# StandaloneAnemometer_RevB.net
KiCad netlist of a schematic drawn in EAGLE
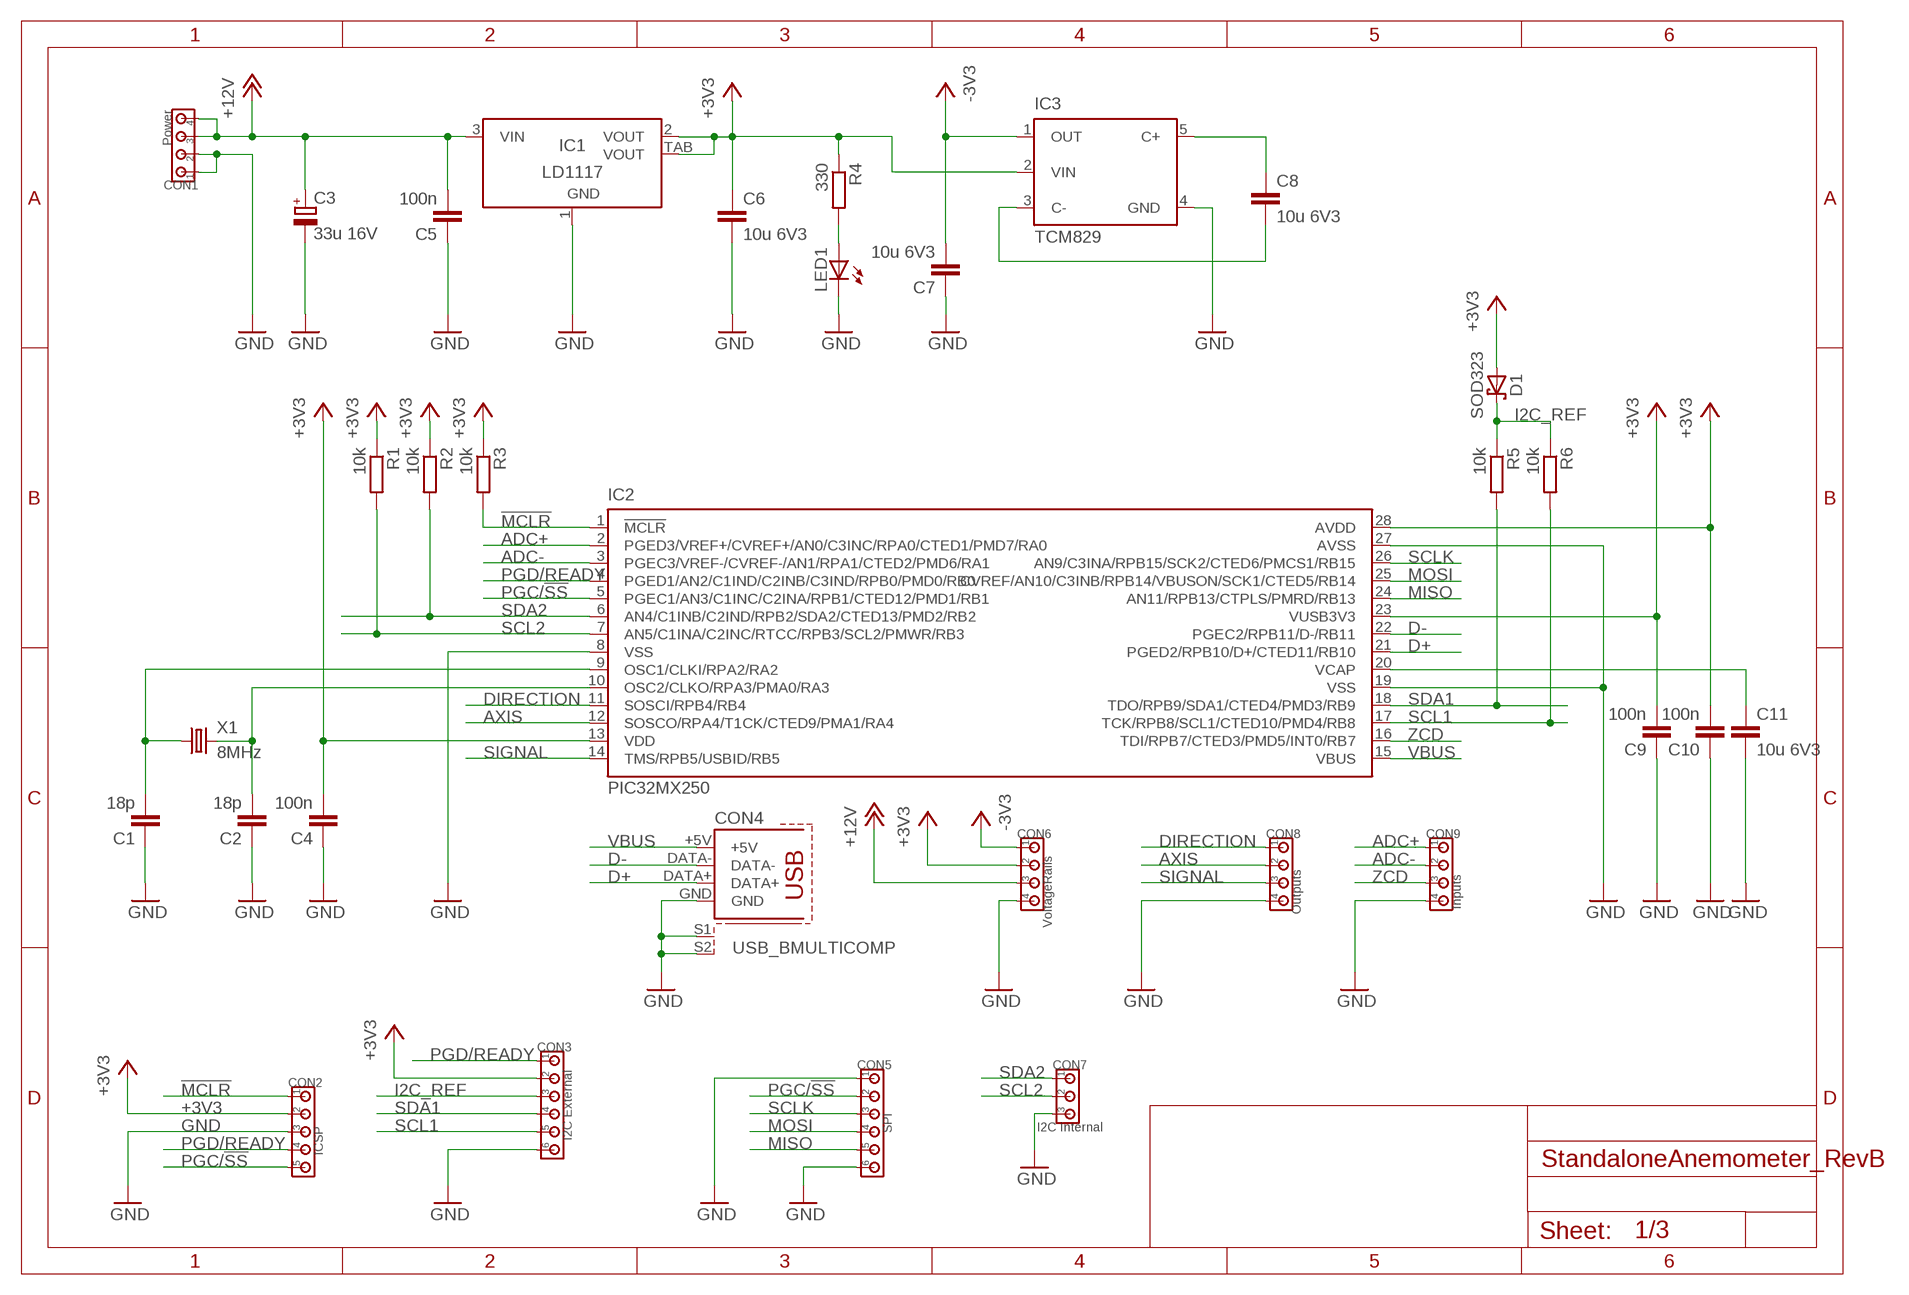
[diagram p0: schematic, sheet 1]
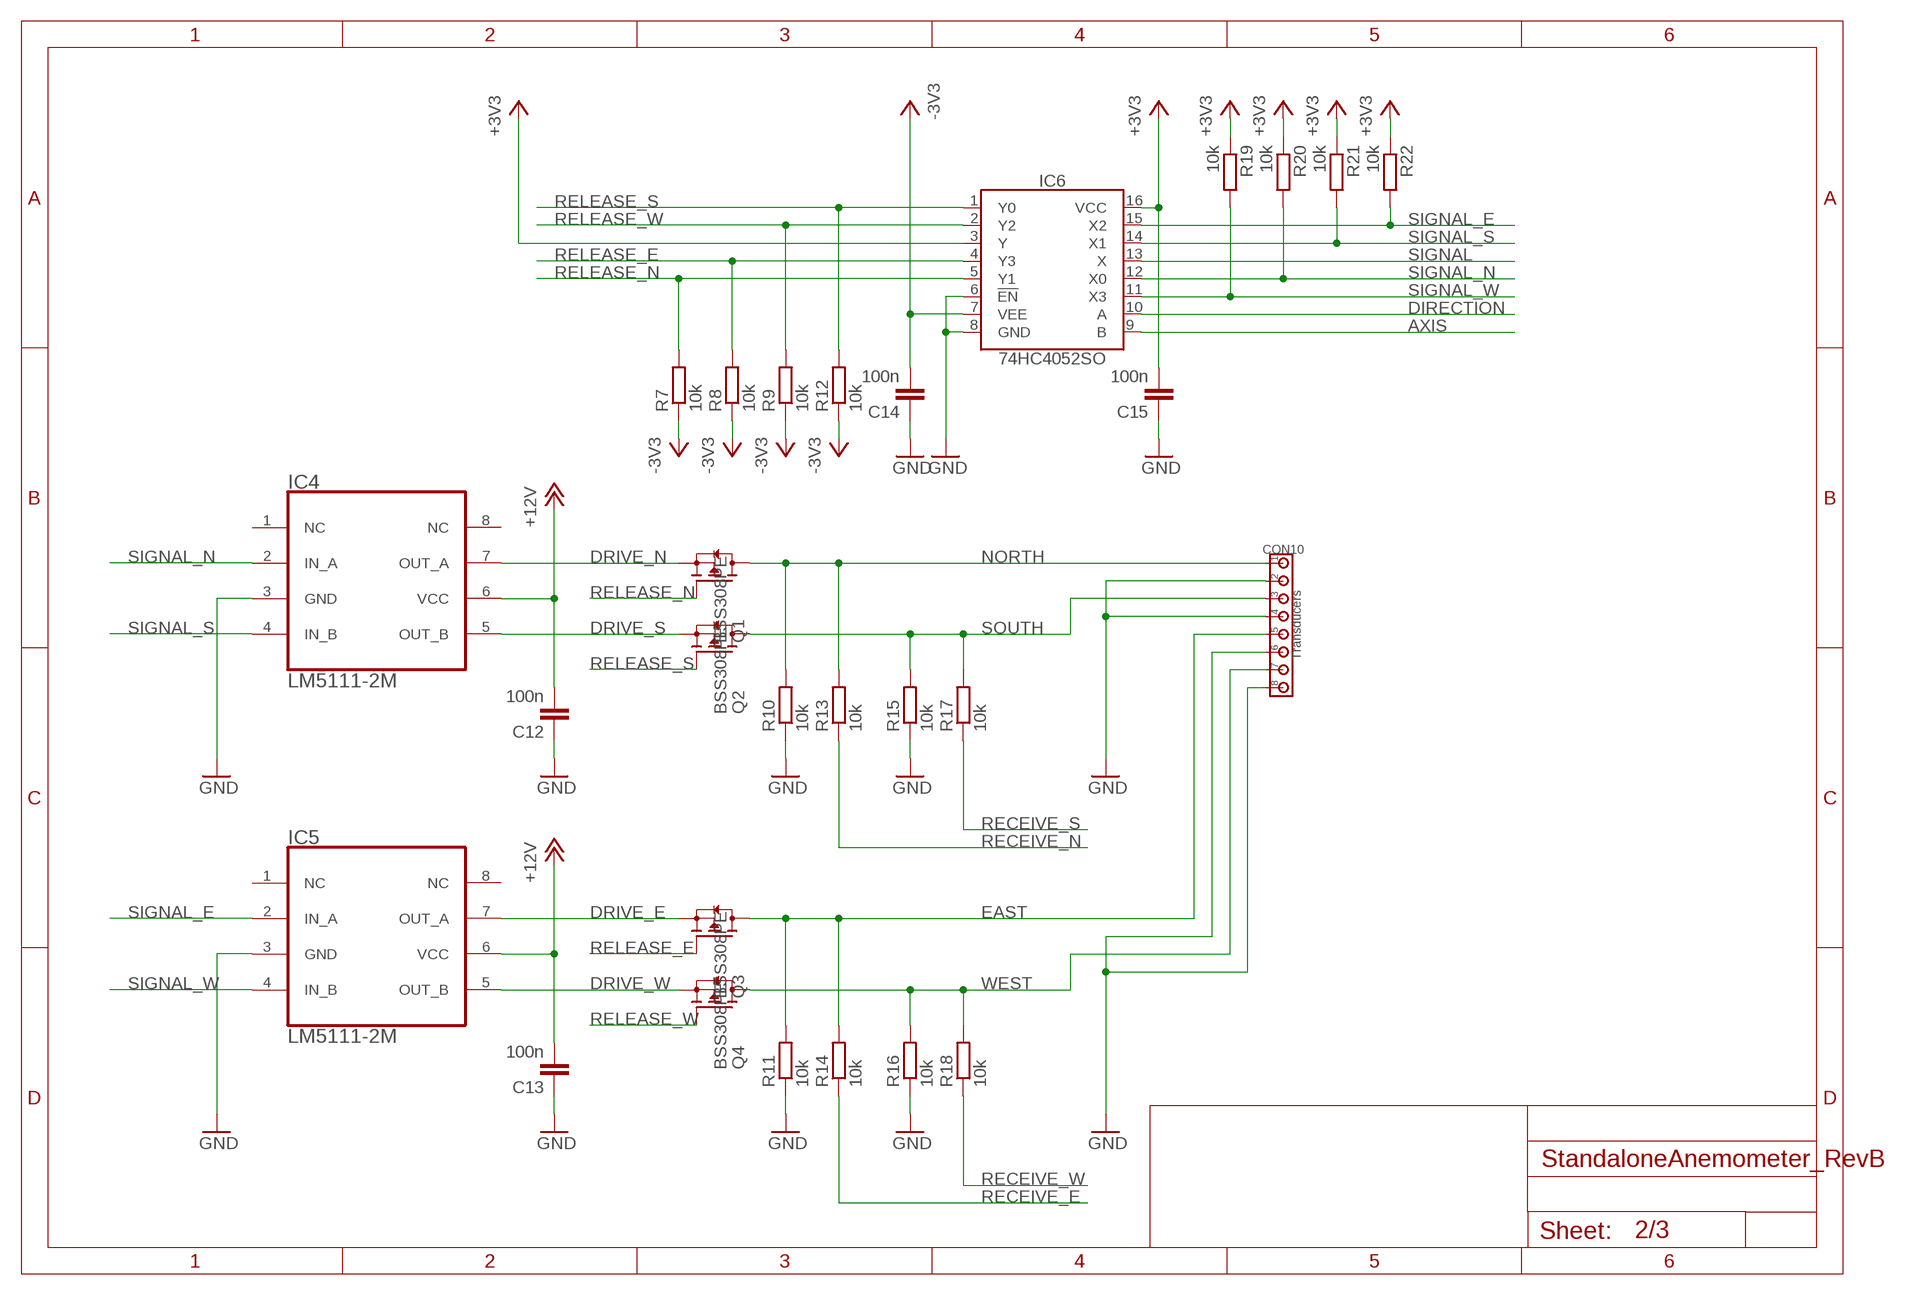
[diagram p1: schematic, sheet 2]
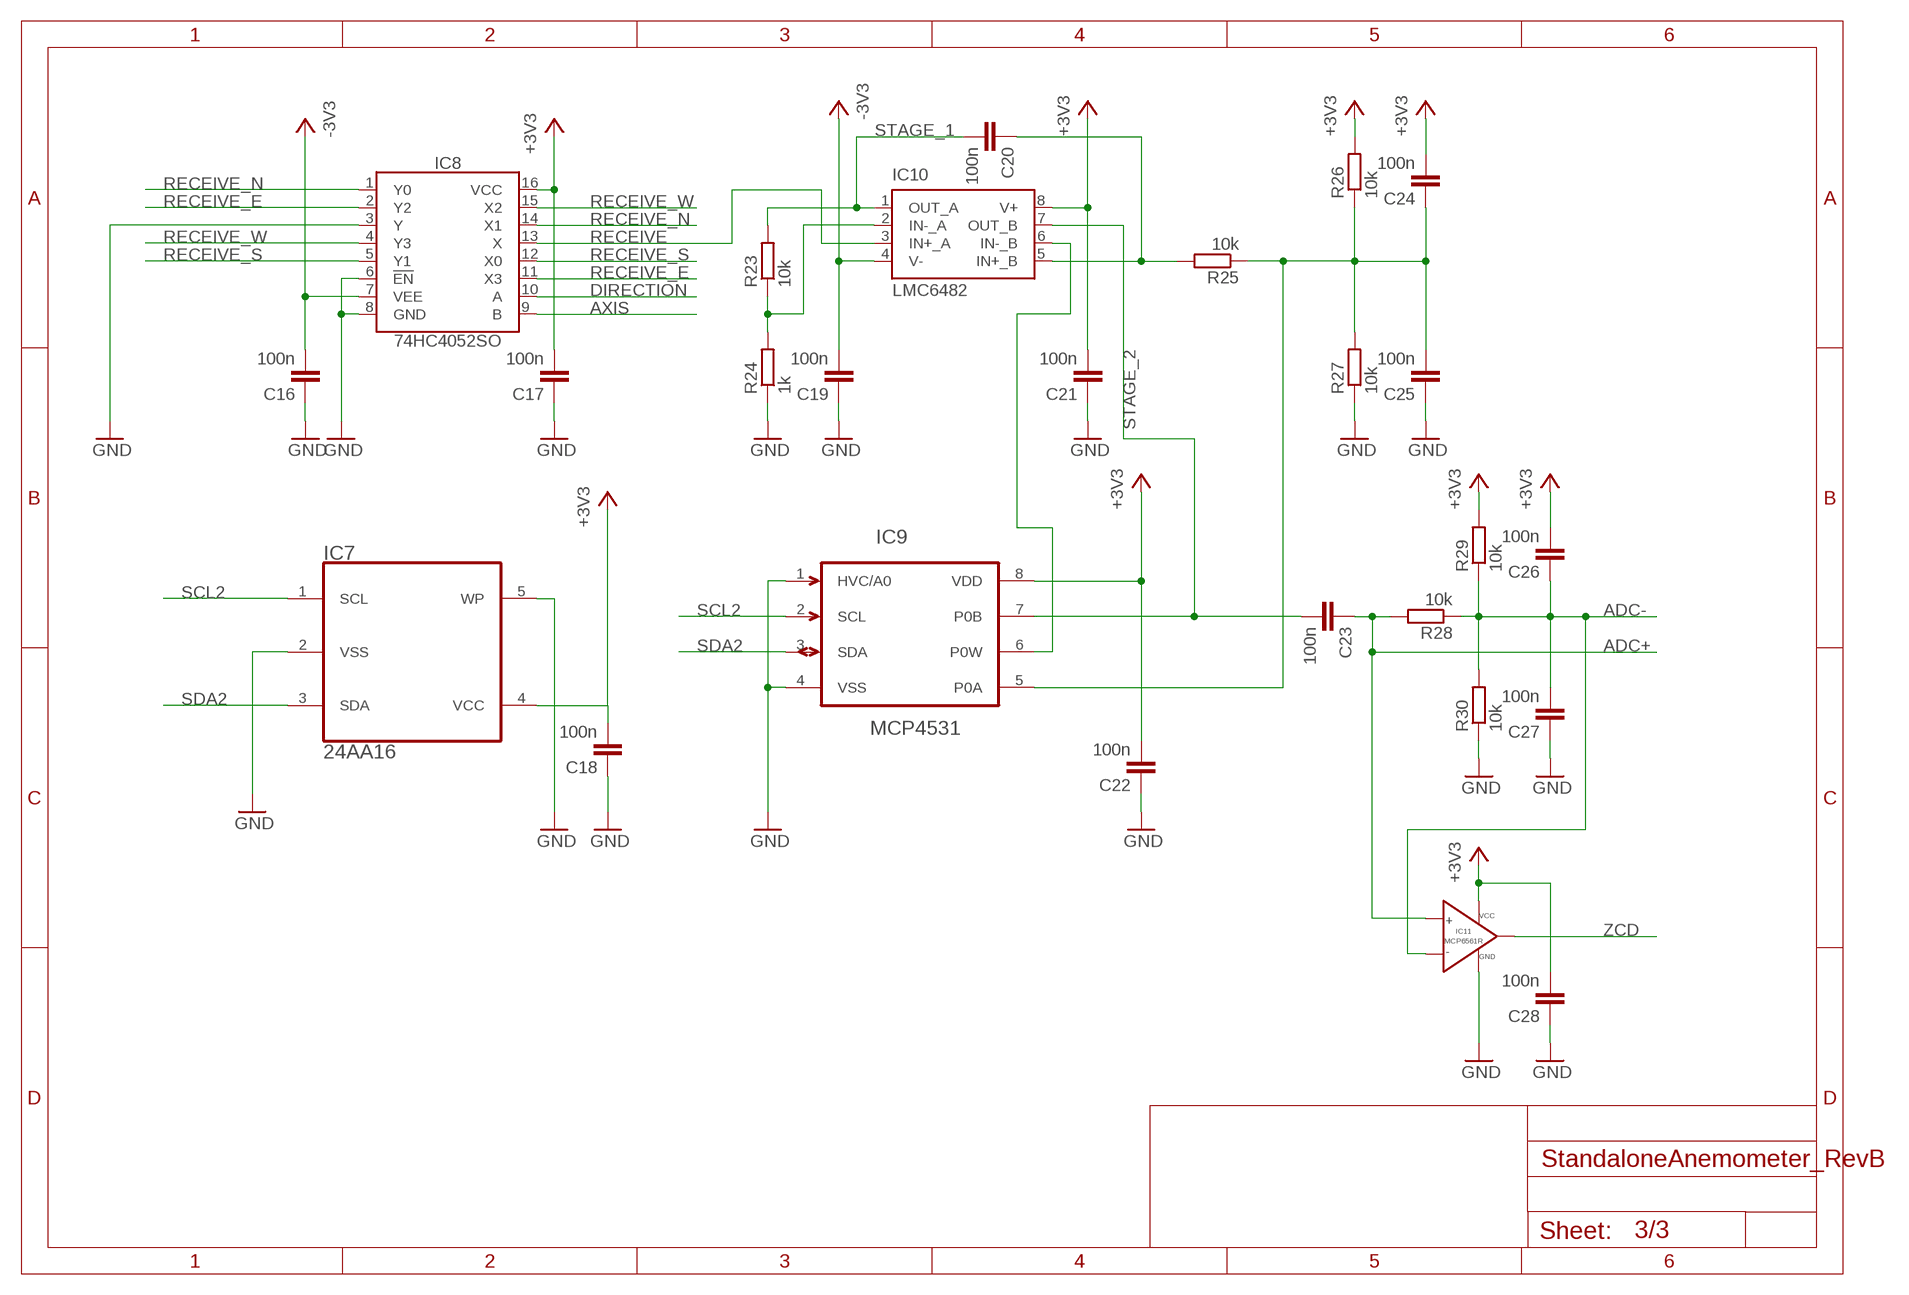
[diagram p2: schematic, sheet 3]

(export (version "E")
  (design (tool "Eeschema 10.0.6"))
  (components
    (comp (ref "C12")
      (value "100n")
      (footprint "eagle-import:C0805")
      (libsource (lib "eagle-import") (part "CC0805"))
    )
    (comp (ref "C13")
      (value "100n")
      (footprint "eagle-import:C0805")
      (libsource (lib "eagle-import") (part "CC0805"))
    )
    (comp (ref "C14")
      (value "100n")
      (footprint "eagle-import:C0805")
      (libsource (lib "eagle-import") (part "CC0805"))
    )
    (comp (ref "C15")
      (value "100n")
      (footprint "eagle-import:C0805")
      (libsource (lib "eagle-import") (part "CC0805"))
    )
    (comp (ref "CON10")
      (value "Transducers")
      (footprint "eagle-import:100MIL_8X")
      (libsource (lib "eagle-import") (part "CON_8X"))
    )
    (comp (ref "IC4")
      (value "LM5111-2M")
      (footprint "eagle-import:SOIC8")
      (libsource (lib "eagle-import") (part "LM5111"))
    )
    (comp (ref "IC5")
      (value "LM5111-2M")
      (footprint "eagle-import:SOIC8")
      (libsource (lib "eagle-import") (part "LM5111"))
    )
    (comp (ref "IC6")
      (value "74HC4052SO")
      (footprint "eagle-import:SO16")
      (libsource (lib "eagle-import") (part "74HC4052SO"))
    )
    (comp (ref "Q1")
      (value "BSS308PE")
      (footprint "eagle-import:SOT23")
      (libsource (lib "eagle-import") (part "P-FET"))
    )
    (comp (ref "Q2")
      (value "BSS308PE")
      (footprint "eagle-import:SOT23")
      (libsource (lib "eagle-import") (part "P-FET"))
    )
    (comp (ref "Q3")
      (value "BSS308PE")
      (footprint "eagle-import:SOT23")
      (libsource (lib "eagle-import") (part "P-FET"))
    )
    (comp (ref "Q4")
      (value "BSS308PE")
      (footprint "eagle-import:SOT23")
      (libsource (lib "eagle-import") (part "P-FET"))
    )
    (comp (ref "R7")
      (value "10k")
      (footprint "eagle-import:R0805")
      (libsource (lib "eagle-import") (part "RESISTORR0805"))
    )
    (comp (ref "R8")
      (value "10k")
      (footprint "eagle-import:R0805")
      (libsource (lib "eagle-import") (part "RESISTORR0805"))
    )
    (comp (ref "R9")
      (value "10k")
      (footprint "eagle-import:R0805")
      (libsource (lib "eagle-import") (part "RESISTORR0805"))
    )
    (comp (ref "R10")
      (value "10k")
      (footprint "eagle-import:R0805")
      (libsource (lib "eagle-import") (part "RESISTORR0805"))
    )
    (comp (ref "R11")
      (value "10k")
      (footprint "eagle-import:R0805")
      (libsource (lib "eagle-import") (part "RESISTORR0805"))
    )
    (comp (ref "R12")
      (value "10k")
      (footprint "eagle-import:R0805")
      (libsource (lib "eagle-import") (part "RESISTORR0805"))
    )
    (comp (ref "R13")
      (value "10k")
      (footprint "eagle-import:R0805")
      (libsource (lib "eagle-import") (part "RESISTORR0805"))
    )
    (comp (ref "R14")
      (value "10k")
      (footprint "eagle-import:R0805")
      (libsource (lib "eagle-import") (part "RESISTORR0805"))
    )
    (comp (ref "R15")
      (value "10k")
      (footprint "eagle-import:R0805")
      (libsource (lib "eagle-import") (part "RESISTORR0805"))
    )
    (comp (ref "R16")
      (value "10k")
      (footprint "eagle-import:R0805")
      (libsource (lib "eagle-import") (part "RESISTORR0805"))
    )
    (comp (ref "R17")
      (value "10k")
      (footprint "eagle-import:R0805")
      (libsource (lib "eagle-import") (part "RESISTORR0805"))
    )
    (comp (ref "R18")
      (value "10k")
      (footprint "eagle-import:R0805")
      (libsource (lib "eagle-import") (part "RESISTORR0805"))
    )
    (comp (ref "R19")
      (value "10k")
      (footprint "eagle-import:R0805")
      (libsource (lib "eagle-import") (part "RESISTORR0805"))
    )
    (comp (ref "R20")
      (value "10k")
      (footprint "eagle-import:R0805")
      (libsource (lib "eagle-import") (part "RESISTORR0805"))
    )
    (comp (ref "R21")
      (value "10k")
      (footprint "eagle-import:R0805")
      (libsource (lib "eagle-import") (part "RESISTORR0805"))
    )
    (comp (ref "R22")
      (value "10k")
      (footprint "eagle-import:R0805")
      (libsource (lib "eagle-import") (part "RESISTORR0805"))
    )
    (comp (ref "C1")
      (value "18p")
      (footprint "eagle-import:C0805")
      (libsource (lib "eagle-import") (part "CC0805"))
    )
    (comp (ref "C2")
      (value "18p")
      (footprint "eagle-import:C0805")
      (libsource (lib "eagle-import") (part "CC0805"))
    )
    (comp (ref "C3")
      (value "33u 16V")
      (footprint "eagle-import:SMC_B")
      (libsource (lib "eagle-import") (part "C_POLARIZEDSMC_B"))
    )
    (comp (ref "C4")
      (value "100n")
      (footprint "eagle-import:C0805")
      (libsource (lib "eagle-import") (part "CC0805"))
    )
    (comp (ref "C5")
      (value "100n")
      (footprint "eagle-import:C0805")
      (libsource (lib "eagle-import") (part "CC0805"))
    )
    (comp (ref "C6")
      (value "10u 6V3")
      (footprint "eagle-import:C0805")
      (libsource (lib "eagle-import") (part "CC0805"))
    )
    (comp (ref "C7")
      (value "10u 6V3")
      (footprint "eagle-import:C0805")
      (libsource (lib "eagle-import") (part "CC0805"))
    )
    (comp (ref "C8")
      (value "10u 6V3")
      (footprint "eagle-import:C0805")
      (libsource (lib "eagle-import") (part "CC0805"))
    )
    (comp (ref "C9")
      (value "100n")
      (footprint "eagle-import:C0805")
      (libsource (lib "eagle-import") (part "CC0805"))
    )
    (comp (ref "C10")
      (value "100n")
      (footprint "eagle-import:C0805")
      (libsource (lib "eagle-import") (part "CC0805"))
    )
    (comp (ref "C11")
      (value "10u 6V3")
      (footprint "eagle-import:C0805")
      (libsource (lib "eagle-import") (part "CC0805"))
    )
    (comp (ref "CON1")
      (value "Power")
      (footprint "eagle-import:100MIL_4X")
      (libsource (lib "eagle-import") (part "CON_4X100MIL"))
    )
    (comp (ref "CON2")
      (value "ICSP")
      (footprint "eagle-import:100MIL_5X")
      (libsource (lib "eagle-import") (part "CON_5X100MIL"))
    )
    (comp (ref "CON3")
      (value "I2C External")
      (footprint "eagle-import:100MIL_6X")
      (libsource (lib "eagle-import") (part "CON_6X100MIL"))
    )
    (comp (ref "CON4")
      (value "USB_BMULTICOMP")
      (footprint "eagle-import:USB_B")
      (libsource (lib "eagle-import") (part "USB_BMULTICOMP"))
    )
    (comp (ref "CON5")
      (value "SPI")
      (footprint "eagle-import:100MIL_6X")
      (libsource (lib "eagle-import") (part "CON_6X100MIL"))
    )
    (comp (ref "CON6")
      (value "VoltageRails")
      (footprint "eagle-import:100MIL_4X")
      (libsource (lib "eagle-import") (part "CON_4X100MIL"))
    )
    (comp (ref "CON7")
      (value "I2C Internal")
      (footprint "eagle-import:100MIL_3X")
      (libsource (lib "eagle-import") (part "CON_3X100MIL"))
    )
    (comp (ref "CON8")
      (value "Outputs")
      (footprint "eagle-import:100MIL_4X")
      (libsource (lib "eagle-import") (part "CON_4X100MIL"))
    )
    (comp (ref "CON9")
      (value "Inputs")
      (footprint "eagle-import:100MIL_4X")
      (libsource (lib "eagle-import") (part "CON_4X100MIL"))
    )
    (comp (ref "D1")
      (value "SOD323")
      (footprint "eagle-import:SOD323")
      (libsource (lib "eagle-import") (part "SCHOTTKYSOD323"))
    )
    (comp (ref "IC1")
      (value "LD1117")
      (footprint "eagle-import:SOT223")
      (libsource (lib "eagle-import") (part "LD1117"))
    )
    (comp (ref "IC2")
      (value "PIC32MX250")
      (footprint "eagle-import:SO28W")
      (libsource (lib "eagle-import") (part "PIC32MX2XX"))
    )
    (comp (ref "IC3")
      (value "TCM829")
      (footprint "eagle-import:SOT-23-5")
      (libsource (lib "eagle-import") (part "TCM829"))
    )
    (comp (ref "LED1")
      (value "LED0805")
      (footprint "eagle-import:LED0805")
      (libsource (lib "eagle-import") (part "LED0805"))
    )
    (comp (ref "R1")
      (value "10k")
      (footprint "eagle-import:R0805")
      (libsource (lib "eagle-import") (part "RESISTORR0805"))
    )
    (comp (ref "R2")
      (value "10k")
      (footprint "eagle-import:R0805")
      (libsource (lib "eagle-import") (part "RESISTORR0805"))
    )
    (comp (ref "R3")
      (value "10k")
      (footprint "eagle-import:R0805")
      (libsource (lib "eagle-import") (part "RESISTORR0805"))
    )
    (comp (ref "R4")
      (value "330")
      (footprint "eagle-import:R0805")
      (libsource (lib "eagle-import") (part "RESISTORR0805"))
    )
    (comp (ref "R5")
      (value "10k")
      (footprint "eagle-import:R0805")
      (libsource (lib "eagle-import") (part "RESISTORR0805"))
    )
    (comp (ref "R6")
      (value "10k")
      (footprint "eagle-import:R0805")
      (libsource (lib "eagle-import") (part "RESISTORR0805"))
    )
    (comp (ref "X1")
      (value "8MHz")
      (footprint "eagle-import:5X3.2MM")
      (libsource (lib "eagle-import") (part "CRYSTAL5X3.2MM"))
    )
    (comp (ref "C16")
      (value "100n")
      (footprint "eagle-import:C0805")
      (libsource (lib "eagle-import") (part "CC0805"))
    )
    (comp (ref "C17")
      (value "100n")
      (footprint "eagle-import:C0805")
      (libsource (lib "eagle-import") (part "CC0805"))
    )
    (comp (ref "C18")
      (value "100n")
      (footprint "eagle-import:C0805")
      (libsource (lib "eagle-import") (part "CC0805"))
    )
    (comp (ref "C19")
      (value "100n")
      (footprint "eagle-import:C0805")
      (libsource (lib "eagle-import") (part "CC0805"))
    )
    (comp (ref "C20")
      (value "100n")
      (footprint "eagle-import:C0805")
      (libsource (lib "eagle-import") (part "CC0805"))
    )
    (comp (ref "C21")
      (value "100n")
      (footprint "eagle-import:C0805")
      (libsource (lib "eagle-import") (part "CC0805"))
    )
    (comp (ref "C22")
      (value "100n")
      (footprint "eagle-import:C0805")
      (libsource (lib "eagle-import") (part "CC0805"))
    )
    (comp (ref "C23")
      (value "100n")
      (footprint "eagle-import:C0805")
      (libsource (lib "eagle-import") (part "CC0805"))
    )
    (comp (ref "C24")
      (value "100n")
      (footprint "eagle-import:C0805")
      (libsource (lib "eagle-import") (part "CC0805"))
    )
    (comp (ref "C25")
      (value "100n")
      (footprint "eagle-import:C0805")
      (libsource (lib "eagle-import") (part "CC0805"))
    )
    (comp (ref "C26")
      (value "100n")
      (footprint "eagle-import:C0805")
      (libsource (lib "eagle-import") (part "CC0805"))
    )
    (comp (ref "C27")
      (value "100n")
      (footprint "eagle-import:C0805")
      (libsource (lib "eagle-import") (part "CC0805"))
    )
    (comp (ref "C28")
      (value "100n")
      (footprint "eagle-import:C0805")
      (libsource (lib "eagle-import") (part "CC0805"))
    )
    (comp (ref "IC7")
      (value "24AA16")
      (footprint "eagle-import:SOT-23-5")
      (libsource (lib "eagle-import") (part "24AA16"))
    )
    (comp (ref "IC8")
      (value "74HC4052SO")
      (footprint "eagle-import:SO16")
      (libsource (lib "eagle-import") (part "74HC4052SO"))
    )
    (comp (ref "IC9")
      (value "MCP4531")
      (footprint "eagle-import:MSOP")
      (libsource (lib "eagle-import") (part "MCP4531"))
    )
    (comp (ref "IC10")
      (value "LMC6482")
      (footprint "eagle-import:SOIC8")
      (libsource (lib "eagle-import") (part "LMC6482"))
    )
    (comp (ref "IC11")
      (value "MCP6561R")
      (footprint "eagle-import:SOT-23-5")
      (libsource (lib "eagle-import") (part "MCP6561R"))
    )
    (comp (ref "R23")
      (value "10k")
      (footprint "eagle-import:R0805")
      (libsource (lib "eagle-import") (part "RESISTORR0805"))
    )
    (comp (ref "R24")
      (value "1k")
      (footprint "eagle-import:R0805")
      (libsource (lib "eagle-import") (part "RESISTORR0805"))
    )
    (comp (ref "R25")
      (value "10k")
      (footprint "eagle-import:R0805")
      (libsource (lib "eagle-import") (part "RESISTORR0805"))
    )
    (comp (ref "R26")
      (value "10k")
      (footprint "eagle-import:R0805")
      (libsource (lib "eagle-import") (part "RESISTORR0805"))
    )
    (comp (ref "R27")
      (value "10k")
      (footprint "eagle-import:R0805")
      (libsource (lib "eagle-import") (part "RESISTORR0805"))
    )
    (comp (ref "R28")
      (value "10k")
      (footprint "eagle-import:R0805")
      (libsource (lib "eagle-import") (part "RESISTORR0805"))
    )
    (comp (ref "R29")
      (value "10k")
      (footprint "eagle-import:R0805")
      (libsource (lib "eagle-import") (part "RESISTORR0805"))
    )
    (comp (ref "R30")
      (value "10k")
      (footprint "eagle-import:R0805")
      (libsource (lib "eagle-import") (part "RESISTORR0805"))
    )
  )
  (nets
    (net (code "1") (name "+3V3") (class "Default")
      (node (ref "C10") (pin "2") (pinfunction "2_2") (pintype "passive"))
      (node (ref "C15") (pin "2") (pinfunction "2_2") (pintype "passive"))
      (node (ref "C17") (pin "2") (pinfunction "2_2") (pintype "passive"))
      (node (ref "C18") (pin "2") (pinfunction "2_2") (pintype "passive"))
      (node (ref "C21") (pin "2") (pinfunction "2_2") (pintype "passive"))
      (node (ref "C22") (pin "2") (pinfunction "2_2") (pintype "passive"))
      (node (ref "C24") (pin "2") (pinfunction "2_2") (pintype "passive"))
      (node (ref "C26") (pin "2") (pinfunction "2_2") (pintype "passive"))
      (node (ref "C28") (pin "2") (pinfunction "2_2") (pintype "passive"))
      (node (ref "C4") (pin "2") (pinfunction "2_2") (pintype "passive"))
      (node (ref "C6") (pin "1") (pinfunction "1_1") (pintype "passive"))
      (node (ref "C9") (pin "2") (pinfunction "2_2") (pintype "passive"))
      (node (ref "CON2") (pin "2") (pinfunction "2_2") (pintype "passive"))
      (node (ref "CON3") (pin "2") (pinfunction "2_2") (pintype "passive"))
      (node (ref "CON6") (pin "2") (pinfunction "2_2") (pintype "passive"))
      (node (ref "D1") (pin "A") (pinfunction "A_A") (pintype "passive"))
      (node (ref "IC1") (pin "2") (pinfunction "VOUT_2") (pintype "output"))
      (node (ref "IC1") (pin "TAB") (pinfunction "VOUT_TAB") (pintype "output"))
      (node (ref "IC10") (pin "8") (pinfunction "V+_8") (pintype "input"))
      (node (ref "IC11") (pin "2") (pinfunction "VCC_2") (pintype "input"))
      (node (ref "IC2") (pin "13") (pinfunction "VDD_13") (pintype "bidirectional"))
      (node (ref "IC2") (pin "23") (pinfunction "VUSB3V3_23") (pintype "bidirectional"))
      (node (ref "IC2") (pin "28") (pinfunction "AVDD_28") (pintype "bidirectional"))
      (node (ref "IC3") (pin "2") (pinfunction "VIN_2") (pintype "passive"))
      (node (ref "IC6") (pin "16") (pinfunction "VCC_16") (pintype "power_in"))
      (node (ref "IC6") (pin "3") (pinfunction "Y_3") (pintype "input"))
      (node (ref "IC7") (pin "4") (pinfunction "VCC_4") (pintype "power_in"))
      (node (ref "IC8") (pin "16") (pinfunction "VCC_16") (pintype "power_in"))
      (node (ref "IC9") (pin "8") (pinfunction "VDD_8") (pintype "power_in"))
      (node (ref "R1") (pin "1") (pinfunction "1_1") (pintype "passive"))
      (node (ref "R19") (pin "1") (pinfunction "1_1") (pintype "passive"))
      (node (ref "R2") (pin "1") (pinfunction "1_1") (pintype "passive"))
      (node (ref "R20") (pin "1") (pinfunction "1_1") (pintype "passive"))
      (node (ref "R21") (pin "1") (pinfunction "1_1") (pintype "passive"))
      (node (ref "R22") (pin "1") (pinfunction "1_1") (pintype "passive"))
      (node (ref "R26") (pin "2") (pinfunction "2_2") (pintype "passive"))
      (node (ref "R29") (pin "2") (pinfunction "2_2") (pintype "passive"))
      (node (ref "R3") (pin "1") (pinfunction "1_1") (pintype "passive"))
      (node (ref "R4") (pin "1") (pinfunction "1_1") (pintype "passive"))
    )
    (net (code "2") (name "+12V") (class "Default")
      (node (ref "C12") (pin "2") (pinfunction "2_2") (pintype "passive"))
      (node (ref "C13") (pin "2") (pinfunction "2_2") (pintype "passive"))
      (node (ref "C3") (pin "+") (pinfunction "+_+") (pintype "passive"))
      (node (ref "C5") (pin "2") (pinfunction "2_2") (pintype "passive"))
      (node (ref "CON1") (pin "3") (pinfunction "3_3") (pintype "passive"))
      (node (ref "CON1") (pin "4") (pinfunction "4_4") (pintype "passive"))
      (node (ref "CON6") (pin "3") (pinfunction "3_3") (pintype "passive"))
      (node (ref "IC1") (pin "3") (pinfunction "VIN_3") (pintype "passive"))
      (node (ref "IC4") (pin "6") (pinfunction "VCC_6") (pintype "input"))
      (node (ref "IC5") (pin "6") (pinfunction "VCC_6") (pintype "input"))
    )
    (net (code "3") (name "-3V3") (class "Default")
      (node (ref "C14") (pin "2") (pinfunction "2_2") (pintype "passive"))
      (node (ref "C16") (pin "2") (pinfunction "2_2") (pintype "passive"))
      (node (ref "C19") (pin "2") (pinfunction "2_2") (pintype "passive"))
      (node (ref "C7") (pin "2") (pinfunction "2_2") (pintype "passive"))
      (node (ref "CON6") (pin "1") (pinfunction "1_1") (pintype "passive"))
      (node (ref "IC10") (pin "4") (pinfunction "V-_4") (pintype "power_in"))
      (node (ref "IC3") (pin "1") (pinfunction "OUT_1") (pintype "passive"))
      (node (ref "IC6") (pin "7") (pinfunction "VEE_7") (pintype "bidirectional"))
      (node (ref "IC8") (pin "7") (pinfunction "VEE_7") (pintype "bidirectional"))
      (node (ref "R12") (pin "1") (pinfunction "1_1") (pintype "passive"))
      (node (ref "R7") (pin "1") (pinfunction "1_1") (pintype "passive"))
      (node (ref "R8") (pin "1") (pinfunction "1_1") (pintype "passive"))
      (node (ref "R9") (pin "1") (pinfunction "1_1") (pintype "passive"))
    )
    (net (code "4") (name "ADC+") (class "Default")
      (node (ref "C23") (pin "1") (pinfunction "1_1") (pintype "passive"))
      (node (ref "CON9") (pin "1") (pinfunction "1_1") (pintype "passive"))
      (node (ref "IC11") (pin "3") (pinfunction "VIN+_3") (pintype "input"))
      (node (ref "IC2") (pin "2") (pinfunction "PGED3/VREF+/CVREF+/AN0/C3INC/RPA0/CTED1/PMD7/RA0_2") (pintype "bidirectional"))
      (node (ref "R28") (pin "2") (pinfunction "2_2") (pintype "passive"))
    )
    (net (code "5") (name "ADC-") (class "Default")
      (node (ref "C26") (pin "1") (pinfunction "1_1") (pintype "passive"))
      (node (ref "C27") (pin "2") (pinfunction "2_2") (pintype "passive"))
      (node (ref "CON9") (pin "2") (pinfunction "2_2") (pintype "passive"))
      (node (ref "IC11") (pin "4") (pinfunction "VIN-_4") (pintype "input"))
      (node (ref "IC2") (pin "3") (pinfunction "PGEC3/VREF-/CVREF-/AN1/RPA1/CTED2/PMD6/RA1_3") (pintype "bidirectional"))
      (node (ref "R28") (pin "1") (pinfunction "1_1") (pintype "passive"))
      (node (ref "R29") (pin "1") (pinfunction "1_1") (pintype "passive"))
      (node (ref "R30") (pin "2") (pinfunction "2_2") (pintype "passive"))
    )
    (net (code "6") (name "AXIS") (class "Default")
      (node (ref "CON8") (pin "2") (pinfunction "2_2") (pintype "passive"))
      (node (ref "IC2") (pin "12") (pinfunction "SOSCO/RPA4/T1CK/CTED9/PMA1/RA4_12") (pintype "bidirectional"))
      (node (ref "IC6") (pin "9") (pinfunction "B_9") (pintype "bidirectional"))
      (node (ref "IC8") (pin "9") (pinfunction "B_9") (pintype "bidirectional"))
    )
    (net (code "7") (name "D+") (class "Default")
      (node (ref "CON4") (pin "DATA+") (pinfunction "DATA+_DATA+") (pintype "passive"))
      (node (ref "IC2") (pin "21") (pinfunction "PGED2/RPB10/D+/CTED11/RB10_21") (pintype "bidirectional"))
    )
    (net (code "8") (name "D-") (class "Default")
      (node (ref "CON4") (pin "DATA-") (pinfunction "DATA-_DATA-") (pintype "passive"))
      (node (ref "IC2") (pin "22") (pinfunction "PGEC2/RPB11/D-/RB11_22") (pintype "bidirectional"))
    )
    (net (code "9") (name "DIRECTION") (class "Default")
      (node (ref "CON8") (pin "1") (pinfunction "1_1") (pintype "passive"))
      (node (ref "IC2") (pin "11") (pinfunction "SOSCI/RPB4/RB4_11") (pintype "bidirectional"))
      (node (ref "IC6") (pin "10") (pinfunction "A_10") (pintype "bidirectional"))
      (node (ref "IC8") (pin "10") (pinfunction "A_10") (pintype "bidirectional"))
    )
    (net (code "10") (name "DRIVE_E") (class "Default")
      (node (ref "IC5") (pin "7") (pinfunction "OUT_A_7") (pintype "input"))
      (node (ref "Q3") (pin "2") (pinfunction "S_2") (pintype "passive"))
    )
    (net (code "11") (name "DRIVE_N") (class "Default")
      (node (ref "IC4") (pin "7") (pinfunction "OUT_A_7") (pintype "input"))
      (node (ref "Q1") (pin "2") (pinfunction "S_2") (pintype "passive"))
    )
    (net (code "12") (name "DRIVE_S") (class "Default")
      (node (ref "IC4") (pin "5") (pinfunction "OUT_B_5") (pintype "bidirectional"))
      (node (ref "Q2") (pin "2") (pinfunction "S_2") (pintype "passive"))
    )
    (net (code "13") (name "DRIVE_W") (class "Default")
      (node (ref "IC5") (pin "5") (pinfunction "OUT_B_5") (pintype "bidirectional"))
      (node (ref "Q4") (pin "2") (pinfunction "S_2") (pintype "passive"))
    )
    (net (code "14") (name "EAST") (class "Default")
      (node (ref "CON10") (pin "5") (pinfunction "P$5_5") (pintype "passive"))
      (node (ref "Q3") (pin "3") (pinfunction "D_3") (pintype "passive"))
      (node (ref "R11") (pin "2") (pinfunction "2_2") (pintype "passive"))
      (node (ref "R14") (pin "2") (pinfunction "2_2") (pintype "passive"))
    )
    (net (code "15") (name "GND") (class "Default")
      (node (ref "C1") (pin "1") (pinfunction "1_1") (pintype "passive"))
      (node (ref "C10") (pin "1") (pinfunction "1_1") (pintype "passive"))
      (node (ref "C11") (pin "2") (pinfunction "2_2") (pintype "passive"))
      (node (ref "C12") (pin "1") (pinfunction "1_1") (pintype "passive"))
      (node (ref "C13") (pin "1") (pinfunction "1_1") (pintype "passive"))
      (node (ref "C14") (pin "1") (pinfunction "1_1") (pintype "passive"))
      (node (ref "C15") (pin "1") (pinfunction "1_1") (pintype "passive"))
      (node (ref "C16") (pin "1") (pinfunction "1_1") (pintype "passive"))
      (node (ref "C17") (pin "1") (pinfunction "1_1") (pintype "passive"))
      (node (ref "C18") (pin "1") (pinfunction "1_1") (pintype "passive"))
      (node (ref "C19") (pin "1") (pinfunction "1_1") (pintype "passive"))
      (node (ref "C2") (pin "1") (pinfunction "1_1") (pintype "passive"))
      (node (ref "C21") (pin "1") (pinfunction "1_1") (pintype "passive"))
      (node (ref "C22") (pin "1") (pinfunction "1_1") (pintype "passive"))
      (node (ref "C25") (pin "1") (pinfunction "1_1") (pintype "passive"))
      (node (ref "C27") (pin "1") (pinfunction "1_1") (pintype "passive"))
      (node (ref "C28") (pin "1") (pinfunction "1_1") (pintype "passive"))
      (node (ref "C3") (pin "-") (pinfunction "-_-") (pintype "passive"))
      (node (ref "C4") (pin "1") (pinfunction "1_1") (pintype "passive"))
      (node (ref "C5") (pin "1") (pinfunction "1_1") (pintype "passive"))
      (node (ref "C6") (pin "2") (pinfunction "2_2") (pintype "passive"))
      (node (ref "C7") (pin "1") (pinfunction "1_1") (pintype "passive"))
      (node (ref "C9") (pin "1") (pinfunction "1_1") (pintype "passive"))
      (node (ref "CON1") (pin "1") (pinfunction "1_1") (pintype "passive"))
      (node (ref "CON1") (pin "2") (pinfunction "2_2") (pintype "passive"))
      (node (ref "CON10") (pin "2") (pinfunction "P$2_2") (pintype "passive"))
      (node (ref "CON10") (pin "4") (pinfunction "P$4_4") (pintype "passive"))
      (node (ref "CON10") (pin "6") (pinfunction "P$6_6") (pintype "passive"))
      (node (ref "CON10") (pin "8") (pinfunction "P$8_8") (pintype "passive"))
      (node (ref "CON2") (pin "3") (pinfunction "3_3") (pintype "passive"))
      (node (ref "CON3") (pin "6") (pinfunction "6_6") (pintype "passive"))
      (node (ref "CON4") (pin "GND") (pinfunction "GND_GND") (pintype "passive"))
      (node (ref "CON4") (pin "S1") (pinfunction "S1_S1") (pintype "passive"))
      (node (ref "CON4") (pin "S2") (pinfunction "S2_S2") (pintype "passive"))
      (node (ref "CON5") (pin "1") (pinfunction "1_1") (pintype "passive"))
      (node (ref "CON5") (pin "6") (pinfunction "6_6") (pintype "passive"))
      (node (ref "CON6") (pin "4") (pinfunction "4_4") (pintype "passive"))
      (node (ref "CON7") (pin "3") (pinfunction "3_3") (pintype "passive"))
      (node (ref "CON8") (pin "4") (pinfunction "4_4") (pintype "passive"))
      (node (ref "CON9") (pin "4") (pinfunction "4_4") (pintype "passive"))
      (node (ref "IC1") (pin "1") (pinfunction "GND_1") (pintype "power_in"))
      (node (ref "IC11") (pin "5") (pinfunction "GND_5") (pintype "input"))
      (node (ref "IC2") (pin "19") (pinfunction "VSS_19") (pintype "power_in"))
      (node (ref "IC2") (pin "27") (pinfunction "AVSS_27") (pintype "bidirectional"))
      (node (ref "IC2") (pin "8") (pinfunction "VSS_8") (pintype "power_in"))
      (node (ref "IC3") (pin "4") (pinfunction "GND_4") (pintype "output"))
      (node (ref "IC4") (pin "3") (pinfunction "GND_3") (pintype "input"))
      (node (ref "IC5") (pin "3") (pinfunction "GND_3") (pintype "input"))
      (node (ref "IC6") (pin "6") (pinfunction "~{EN}_6") (pintype "input"))
      (node (ref "IC6") (pin "8") (pinfunction "GND_8") (pintype "output"))
      (node (ref "IC7") (pin "2") (pinfunction "VSS_2") (pintype "passive"))
      (node (ref "IC7") (pin "5") (pinfunction "WP_5") (pintype "input"))
      (node (ref "IC8") (pin "3") (pinfunction "Y_3") (pintype "input"))
      (node (ref "IC8") (pin "6") (pinfunction "~{EN}_6") (pintype "input"))
      (node (ref "IC8") (pin "8") (pinfunction "GND_8") (pintype "output"))
      (node (ref "IC9") (pin "1") (pinfunction "HVC/A0_1") (pintype "input"))
      (node (ref "IC9") (pin "4") (pinfunction "VSS_4") (pintype "power_in"))
      (node (ref "LED1") (pin "C") (pinfunction "C_C") (pintype "passive"))
      (node (ref "R10") (pin "1") (pinfunction "1_1") (pintype "passive"))
      (node (ref "R11") (pin "1") (pinfunction "1_1") (pintype "passive"))
      (node (ref "R15") (pin "1") (pinfunction "1_1") (pintype "passive"))
      (node (ref "R16") (pin "1") (pinfunction "1_1") (pintype "passive"))
      (node (ref "R24") (pin "1") (pinfunction "1_1") (pintype "passive"))
      (node (ref "R27") (pin "1") (pinfunction "1_1") (pintype "passive"))
      (node (ref "R30") (pin "1") (pinfunction "1_1") (pintype "passive"))
    )
    (net (code "16") (name "I2C_REF") (class "Default")
      (node (ref "CON3") (pin "3") (pinfunction "3_3") (pintype "passive"))
      (node (ref "D1") (pin "C") (pinfunction "C_C") (pintype "passive"))
      (node (ref "R5") (pin "1") (pinfunction "1_1") (pintype "passive"))
      (node (ref "R6") (pin "1") (pinfunction "1_1") (pintype "passive"))
    )
    (net (code "17") (name "MISO") (class "Default")
      (node (ref "CON5") (pin "5") (pinfunction "5_5") (pintype "passive"))
      (node (ref "IC2") (pin "24") (pinfunction "AN11/RPB13/CTPLS/PMRD/RB13_24") (pintype "bidirectional"))
    )
    (net (code "18") (name "MOSI") (class "Default")
      (node (ref "CON5") (pin "4") (pinfunction "4_4") (pintype "passive"))
      (node (ref "IC2") (pin "25") (pinfunction "CVREF/AN10/C3INB/RPB14/VBUSON/SCK1/CTED5/RB14_25") (pintype "bidirectional"))
    )
    (net (code "19") (name "NORTH") (class "Default")
      (node (ref "CON10") (pin "1") (pinfunction "P$1_1") (pintype "passive"))
      (node (ref "Q1") (pin "3") (pinfunction "D_3") (pintype "passive"))
      (node (ref "R10") (pin "2") (pinfunction "2_2") (pintype "passive"))
      (node (ref "R13") (pin "2") (pinfunction "2_2") (pintype "passive"))
    )
    (net (code "20") (name "Net-(IC2-OSC1{slash}CLKI{slash}RPA2{slash}RA2)") (class "Default")
      (node (ref "C1") (pin "2") (pinfunction "2_2") (pintype "passive"))
      (node (ref "IC2") (pin "9") (pinfunction "OSC1/CLKI/RPA2/RA2_9") (pintype "bidirectional"))
      (node (ref "X1") (pin "1") (pinfunction "1_1") (pintype "passive"))
    )
    (net (code "21") (name "Net-(IC2-OSC2{slash}CLKO{slash}RPA3{slash}PMA0{slash}RA3)") (class "Default")
      (node (ref "C2") (pin "2") (pinfunction "2_2") (pintype "passive"))
      (node (ref "IC2") (pin "10") (pinfunction "OSC2/CLKO/RPA3/PMA0/RA3_10") (pintype "bidirectional"))
      (node (ref "X1") (pin "2") (pinfunction "2_2") (pintype "passive"))
    )
    (net (code "22") (name "Net-(IC2-VCAP)") (class "Default")
      (node (ref "C11") (pin "1") (pinfunction "1_1") (pintype "passive"))
      (node (ref "IC2") (pin "20") (pinfunction "VCAP_20") (pintype "power_in"))
    )
    (net (code "23") (name "Net-(IC3-C+)") (class "Default")
      (node (ref "C8") (pin "1") (pinfunction "1_1") (pintype "passive"))
      (node (ref "IC3") (pin "5") (pinfunction "C+_5") (pintype "output"))
    )
    (net (code "24") (name "Net-(IC3-C-)") (class "Default")
      (node (ref "C8") (pin "2") (pinfunction "2_2") (pintype "passive"))
      (node (ref "IC3") (pin "3") (pinfunction "C-_3") (pintype "passive"))
    )
    (net (code "25") (name "Net-(IC9-P0A)") (class "Default")
      (node (ref "C24") (pin "1") (pinfunction "1_1") (pintype "passive"))
      (node (ref "C25") (pin "2") (pinfunction "2_2") (pintype "passive"))
      (node (ref "IC9") (pin "5") (pinfunction "P0A_5") (pintype "passive"))
      (node (ref "R25") (pin "1") (pinfunction "1_1") (pintype "passive"))
      (node (ref "R26") (pin "1") (pinfunction "1_1") (pintype "passive"))
      (node (ref "R27") (pin "2") (pinfunction "2_2") (pintype "passive"))
    )
    (net (code "26") (name "Net-(IC10-IN+_B)") (class "Default")
      (node (ref "C20") (pin "1") (pinfunction "1_1") (pintype "passive"))
      (node (ref "IC10") (pin "5") (pinfunction "IN+_B_5") (pintype "passive"))
      (node (ref "R25") (pin "2") (pinfunction "2_2") (pintype "passive"))
    )
    (net (code "27") (name "Net-(IC10-IN-_A)") (class "Default")
      (node (ref "IC10") (pin "2") (pinfunction "IN-_A_2") (pintype "input"))
      (node (ref "R23") (pin "1") (pinfunction "1_1") (pintype "passive"))
      (node (ref "R24") (pin "2") (pinfunction "2_2") (pintype "passive"))
    )
    (net (code "28") (name "Net-(IC10-IN-_B)") (class "Default")
      (node (ref "IC10") (pin "6") (pinfunction "IN-_B_6") (pintype "passive"))
      (node (ref "IC9") (pin "6") (pinfunction "P0W_6") (pintype "passive"))
    )
    (net (code "29") (name "Net-(LED1-PadA)") (class "Default")
      (node (ref "LED1") (pin "A") (pinfunction "A_A") (pintype "passive"))
      (node (ref "R4") (pin "2") (pinfunction "2_2") (pintype "passive"))
    )
    (net (code "30") (name "PGC{slash}~{SS}") (class "Default")
      (node (ref "CON2") (pin "5") (pinfunction "5_5") (pintype "passive"))
      (node (ref "CON5") (pin "2") (pinfunction "2_2") (pintype "passive"))
      (node (ref "IC2") (pin "5") (pinfunction "PGEC1/AN3/C1INC/C2INA/RPB1/CTED12/PMD1/RB1_5") (pintype "bidirectional"))
    )
    (net (code "31") (name "PGD{slash}READY") (class "Default")
      (node (ref "CON2") (pin "4") (pinfunction "4_4") (pintype "passive"))
      (node (ref "CON3") (pin "1") (pinfunction "1_1") (pintype "passive"))
      (node (ref "IC2") (pin "4") (pinfunction "PGED1/AN2/C1IND/C2INB/C3IND/RPB0/PMD0/RB0_4") (pintype "bidirectional"))
    )
    (net (code "32") (name "RECEIVE") (class "Default")
      (node (ref "IC10") (pin "3") (pinfunction "IN+_A_3") (pintype "input"))
      (node (ref "IC8") (pin "13") (pinfunction "X_13") (pintype "bidirectional"))
    )
    (net (code "33") (name "RECEIVE_E") (class "Default")
      (node (ref "IC8") (pin "11") (pinfunction "X3_11") (pintype "bidirectional"))
      (node (ref "IC8") (pin "2") (pinfunction "Y2_2") (pintype "input"))
      (node (ref "R14") (pin "1") (pinfunction "1_1") (pintype "passive"))
    )
    (net (code "34") (name "RECEIVE_N") (class "Default")
      (node (ref "IC8") (pin "1") (pinfunction "Y0_1") (pintype "input"))
      (node (ref "IC8") (pin "14") (pinfunction "X1_14") (pintype "bidirectional"))
      (node (ref "R13") (pin "1") (pinfunction "1_1") (pintype "passive"))
    )
    (net (code "35") (name "RECEIVE_S") (class "Default")
      (node (ref "IC8") (pin "12") (pinfunction "X0_12") (pintype "bidirectional"))
      (node (ref "IC8") (pin "5") (pinfunction "Y1_5") (pintype "input"))
      (node (ref "R17") (pin "1") (pinfunction "1_1") (pintype "passive"))
    )
    (net (code "36") (name "RECEIVE_W") (class "Default")
      (node (ref "IC8") (pin "15") (pinfunction "X2_15") (pintype "bidirectional"))
      (node (ref "IC8") (pin "4") (pinfunction "Y3_4") (pintype "input"))
      (node (ref "R18") (pin "1") (pinfunction "1_1") (pintype "passive"))
    )
    (net (code "37") (name "RELEASE_E") (class "Default")
      (node (ref "IC6") (pin "4") (pinfunction "Y3_4") (pintype "input"))
      (node (ref "Q3") (pin "1") (pinfunction "G_1") (pintype "passive"))
      (node (ref "R8") (pin "2") (pinfunction "2_2") (pintype "passive"))
    )
    (net (code "38") (name "RELEASE_N") (class "Default")
      (node (ref "IC6") (pin "5") (pinfunction "Y1_5") (pintype "input"))
      (node (ref "Q1") (pin "1") (pinfunction "G_1") (pintype "passive"))
      (node (ref "R7") (pin "2") (pinfunction "2_2") (pintype "passive"))
    )
    (net (code "39") (name "RELEASE_S") (class "Default")
      (node (ref "IC6") (pin "1") (pinfunction "Y0_1") (pintype "input"))
      (node (ref "Q2") (pin "1") (pinfunction "G_1") (pintype "passive"))
      (node (ref "R12") (pin "2") (pinfunction "2_2") (pintype "passive"))
    )
    (net (code "40") (name "RELEASE_W") (class "Default")
      (node (ref "IC6") (pin "2") (pinfunction "Y2_2") (pintype "input"))
      (node (ref "Q4") (pin "1") (pinfunction "G_1") (pintype "passive"))
      (node (ref "R9") (pin "2") (pinfunction "2_2") (pintype "passive"))
    )
    (net (code "41") (name "SCL1") (class "Default")
      (node (ref "CON3") (pin "5") (pinfunction "5_5") (pintype "passive"))
      (node (ref "IC2") (pin "17") (pinfunction "TCK/RPB8/SCL1/CTED10/PMD4/RB8_17") (pintype "bidirectional"))
      (node (ref "R6") (pin "2") (pinfunction "2_2") (pintype "passive"))
    )
    (net (code "42") (name "SCL2") (class "Default")
      (node (ref "CON7") (pin "2") (pinfunction "2_2") (pintype "passive"))
      (node (ref "IC2") (pin "7") (pinfunction "AN5/C1INA/C2INC/RTCC/RPB3/SCL2/PMWR/RB3_7") (pintype "bidirectional"))
      (node (ref "IC7") (pin "1") (pinfunction "SCL_1") (pintype "input"))
      (node (ref "IC9") (pin "2") (pinfunction "SCL_2") (pintype "input"))
      (node (ref "R1") (pin "2") (pinfunction "2_2") (pintype "passive"))
    )
    (net (code "43") (name "SCLK") (class "Default")
      (node (ref "CON5") (pin "3") (pinfunction "3_3") (pintype "passive"))
      (node (ref "IC2") (pin "26") (pinfunction "AN9/C3INA/RPB15/SCK2/CTED6/PMCS1/RB15_26") (pintype "bidirectional"))
    )
    (net (code "44") (name "SDA1") (class "Default")
      (node (ref "CON3") (pin "4") (pinfunction "4_4") (pintype "passive"))
      (node (ref "IC2") (pin "18") (pinfunction "TDO/RPB9/SDA1/CTED4/PMD3/RB9_18") (pintype "bidirectional"))
      (node (ref "R5") (pin "2") (pinfunction "2_2") (pintype "passive"))
    )
    (net (code "45") (name "SDA2") (class "Default")
      (node (ref "CON7") (pin "1") (pinfunction "1_1") (pintype "passive"))
      (node (ref "IC2") (pin "6") (pinfunction "AN4/C1INB/C2IND/RPB2/SDA2/CTED13/PMD2/RB2_6") (pintype "bidirectional"))
      (node (ref "IC7") (pin "3") (pinfunction "SDA_3") (pintype "bidirectional"))
      (node (ref "IC9") (pin "3") (pinfunction "SDA_3") (pintype "bidirectional"))
      (node (ref "R2") (pin "2") (pinfunction "2_2") (pintype "passive"))
    )
    (net (code "46") (name "SIGNAL") (class "Default")
      (node (ref "CON8") (pin "3") (pinfunction "3_3") (pintype "passive"))
      (node (ref "IC2") (pin "14") (pinfunction "TMS/RPB5/USBID/RB5_14") (pintype "bidirectional"))
      (node (ref "IC6") (pin "13") (pinfunction "X_13") (pintype "bidirectional"))
    )
    (net (code "47") (name "SIGNAL_E") (class "Default")
      (node (ref "IC5") (pin "2") (pinfunction "IN_A_2") (pintype "input"))
      (node (ref "IC6") (pin "15") (pinfunction "X2_15") (pintype "bidirectional"))
      (node (ref "R22") (pin "2") (pinfunction "2_2") (pintype "passive"))
    )
    (net (code "48") (name "SIGNAL_N") (class "Default")
      (node (ref "IC4") (pin "2") (pinfunction "IN_A_2") (pintype "input"))
      (node (ref "IC6") (pin "12") (pinfunction "X0_12") (pintype "bidirectional"))
      (node (ref "R20") (pin "2") (pinfunction "2_2") (pintype "passive"))
    )
    (net (code "49") (name "SIGNAL_S") (class "Default")
      (node (ref "IC4") (pin "4") (pinfunction "IN_B_4") (pintype "passive"))
      (node (ref "IC6") (pin "14") (pinfunction "X1_14") (pintype "bidirectional"))
      (node (ref "R21") (pin "2") (pinfunction "2_2") (pintype "passive"))
    )
    (net (code "50") (name "SIGNAL_W") (class "Default")
      (node (ref "IC5") (pin "4") (pinfunction "IN_B_4") (pintype "passive"))
      (node (ref "IC6") (pin "11") (pinfunction "X3_11") (pintype "bidirectional"))
      (node (ref "R19") (pin "2") (pinfunction "2_2") (pintype "passive"))
    )
    (net (code "51") (name "SOUTH") (class "Default")
      (node (ref "CON10") (pin "3") (pinfunction "P$3_3") (pintype "passive"))
      (node (ref "Q2") (pin "3") (pinfunction "D_3") (pintype "passive"))
      (node (ref "R15") (pin "2") (pinfunction "2_2") (pintype "passive"))
      (node (ref "R17") (pin "2") (pinfunction "2_2") (pintype "passive"))
    )
    (net (code "52") (name "STAGE_1") (class "Default")
      (node (ref "C20") (pin "2") (pinfunction "2_2") (pintype "passive"))
      (node (ref "IC10") (pin "1") (pinfunction "OUT_A_1") (pintype "input"))
      (node (ref "R23") (pin "2") (pinfunction "2_2") (pintype "passive"))
    )
    (net (code "53") (name "STAGE_2") (class "Default")
      (node (ref "C23") (pin "2") (pinfunction "2_2") (pintype "passive"))
      (node (ref "IC10") (pin "7") (pinfunction "OUT_B_7") (pintype "input"))
      (node (ref "IC9") (pin "7") (pinfunction "P0B_7") (pintype "passive"))
    )
    (net (code "54") (name "VBUS") (class "Default")
      (node (ref "CON4") (pin "+5V") (pinfunction "+5V_+5V") (pintype "passive"))
      (node (ref "IC2") (pin "15") (pinfunction "VBUS_15") (pintype "bidirectional"))
    )
    (net (code "55") (name "WEST") (class "Default")
      (node (ref "CON10") (pin "7") (pinfunction "P$7_7") (pintype "passive"))
      (node (ref "Q4") (pin "3") (pinfunction "D_3") (pintype "passive"))
      (node (ref "R16") (pin "2") (pinfunction "2_2") (pintype "passive"))
      (node (ref "R18") (pin "2") (pinfunction "2_2") (pintype "passive"))
    )
    (net (code "56") (name "ZCD") (class "Default")
      (node (ref "CON9") (pin "3") (pinfunction "3_3") (pintype "passive"))
      (node (ref "IC11") (pin "1") (pinfunction "VOUT_1") (pintype "output"))
      (node (ref "IC2") (pin "16") (pinfunction "TDI/RPB7/CTED3/PMD5/INT0/RB7_16") (pintype "bidirectional"))
    )
    (net (code "57") (name "unconnected-(IC4-NC-Pad1)") (class "Default")
      (node (ref "IC4") (pin "1") (pinfunction "NC_1") (pintype "no_connect"))
    )
    (net (code "58") (name "unconnected-(IC4-NC-Pad8)") (class "Default")
      (node (ref "IC4") (pin "8") (pinfunction "NC_8") (pintype "no_connect"))
    )
    (net (code "59") (name "unconnected-(IC5-NC-Pad1)") (class "Default")
      (node (ref "IC5") (pin "1") (pinfunction "NC_1") (pintype "no_connect"))
    )
    (net (code "60") (name "unconnected-(IC5-NC-Pad8)") (class "Default")
      (node (ref "IC5") (pin "8") (pinfunction "NC_8") (pintype "no_connect"))
    )
    (net (code "61") (name "~{MCLR}") (class "Default")
      (node (ref "CON2") (pin "1") (pinfunction "1_1") (pintype "passive"))
      (node (ref "IC2") (pin "1") (pinfunction "~{MCLR}_1") (pintype "input"))
      (node (ref "R3") (pin "2") (pinfunction "2_2") (pintype "passive"))
    )
  )
)
